# Sheet1.net
KiCad netlist of a schematic drawn in Altium Designer
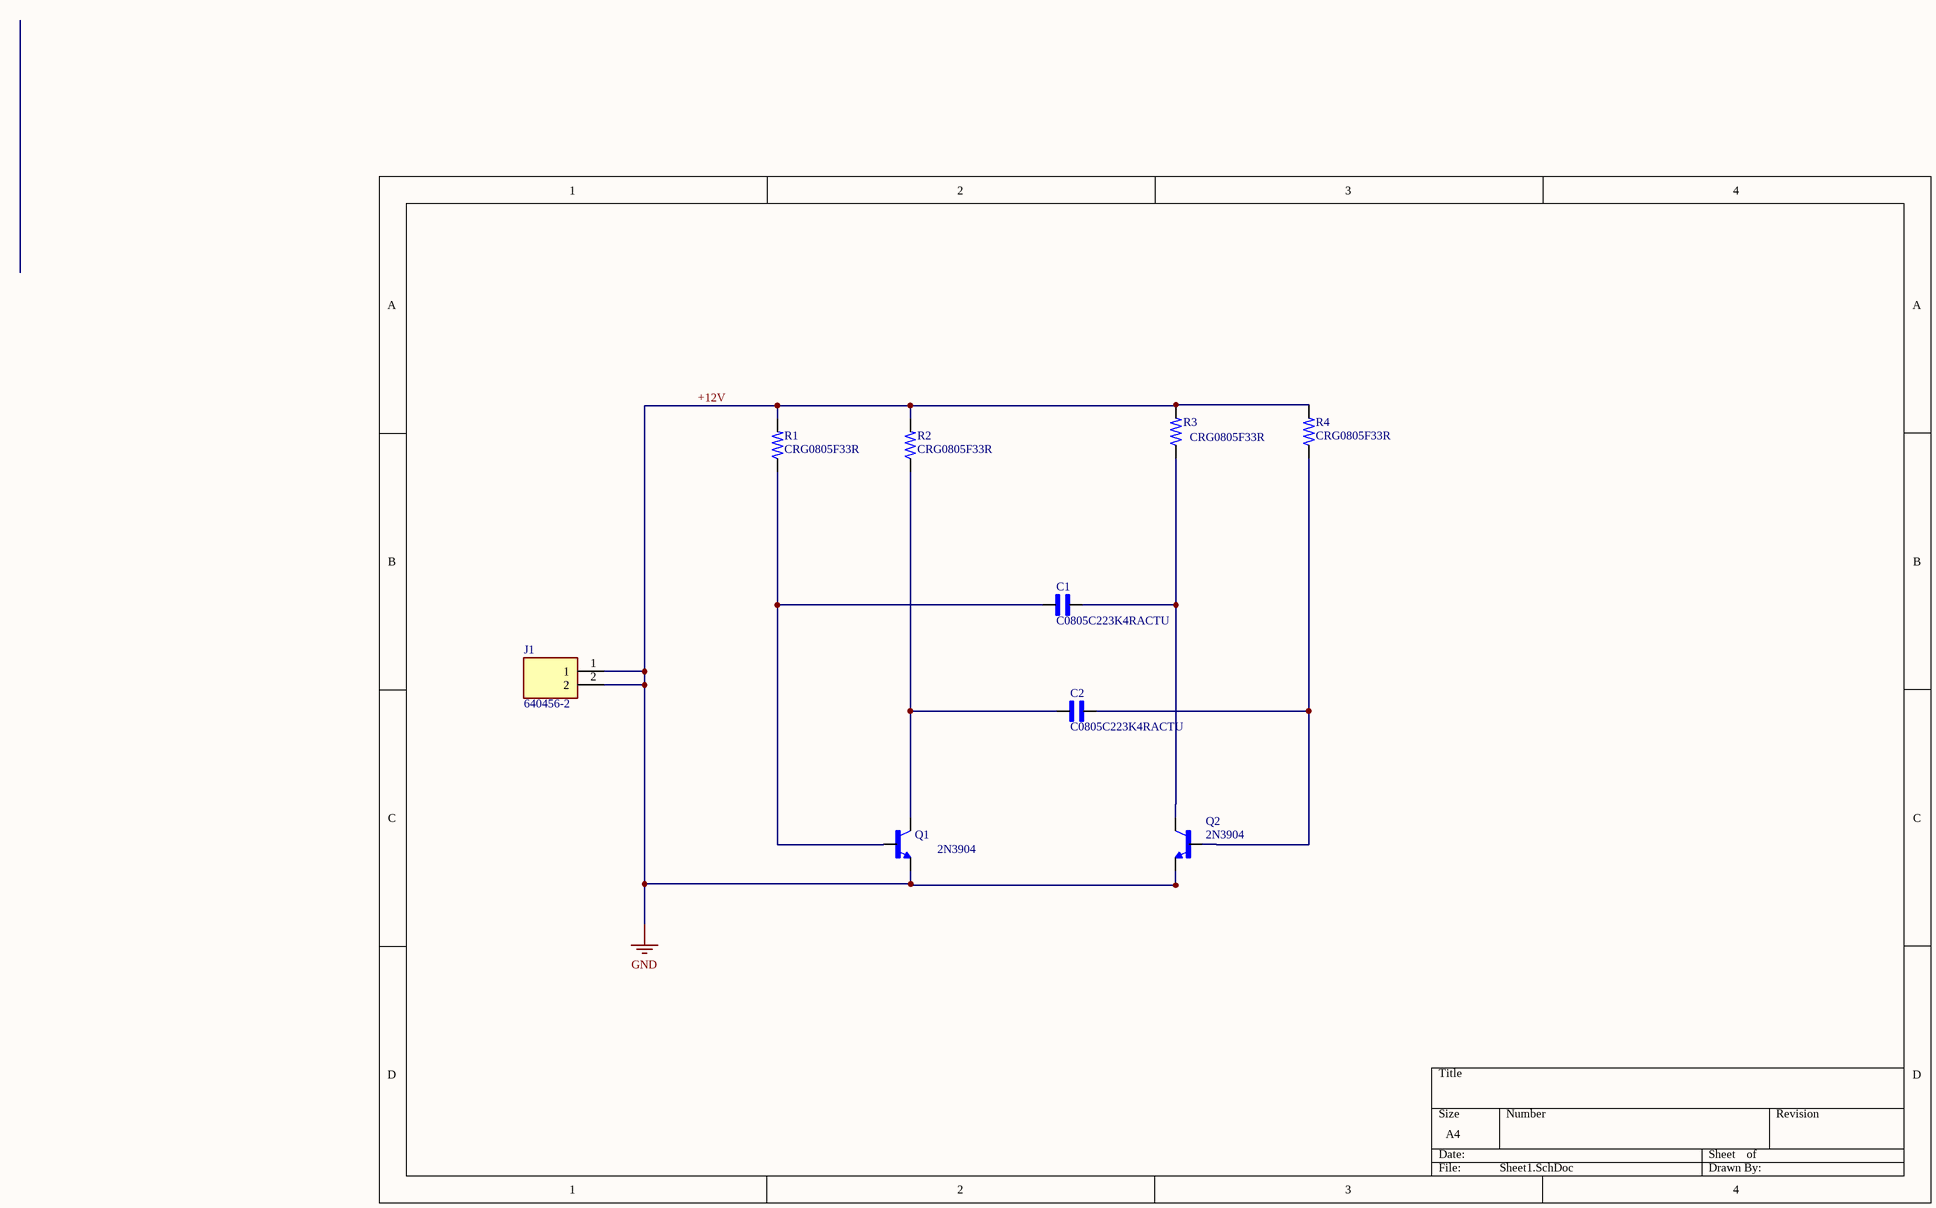
[diagram p0: Sheet1.SchDoc]

(export (version "E")
  (design (tool "Eeschema 10.0.6"))
  (components
    (comp (ref "C1")
      (value "C0805C223K4RACTU")
      (footprint "CAPC2012X88N")
      (description "Capacitor, Ceramic, 22nF, 16VDC, 10-% Tol, 10+% Tol, X7R-TC Code, -15, 15%-TC")
      (fields (field (name "MF") "KEMET"))
      (libsource (lib "C0805C223K4RACTU") (part "C0805C223K4RACTU"))
    )
    (comp (ref "C2")
      (value "C0805C223K4RACTU")
      (footprint "CAPC2012X88N")
      (description "Capacitor, Ceramic, 22nF, 16VDC, 10-% Tol, 10+% Tol, X7R-TC Code, -15, 15%-TC")
      (fields (field (name "MF") "KEMET"))
      (libsource (lib "C0805C223K4RACTU") (part "C0805C223K4RACTU"))
    )
    (comp (ref "J1")
      (value "640456-2")
      (footprint "TE_640456-2")
      (description "Header Friction Lock MTA-100 2 250 VAC Polyester Tin Copper Alloy Tin ¦ TE Connectivity 640456-2")
      (fields (field (name "MF") "TE Connectivity"))
      (libsource (lib "header") (part "640456-2"))
    )
    (comp (ref "Q1")
      (value "2N3904")
      (footprint "TO92254P460H750-3")
      (description "BJT, TO-92, 40V, 200mA, NPN, 0.625W, 150Â°C")
      (fields (field (name "MF") "Diotec Semiconductor"))
      (libsource (lib "2N3904") (part "2N3904"))
    )
    (comp (ref "Q2")
      (value "2N3904")
      (footprint "TO92254P460H750-3")
      (description "BJT, TO-92, 40V, 200mA, NPN, 0.625W, 150Â°C")
      (fields (field (name "MF") "Diotec Semiconductor"))
      (libsource (lib "") (part "2N3904_1"))
    )
    (comp (ref "R1")
      (value "CRG0805F33R")
      (footprint "RESC2012X65N")
      (description "Fixed Resistors")
      (fields (field (name "MF") "TE Connectivity"))
      (libsource (lib "CRG0805F33R") (part "CRG0805F33R"))
    )
    (comp (ref "R2")
      (value "CRG0805F33R")
      (footprint "RESC2012X65N")
      (description "Fixed Resistors")
      (fields (field (name "MF") "TE Connectivity"))
      (libsource (lib "CRG0805F33R") (part "CRG0805F33R"))
    )
    (comp (ref "R3")
      (value "CRG0805F33R")
      (footprint "RESC2012X65N")
      (description "Fixed Resistors")
      (fields (field (name "MF") "TE Connectivity"))
      (libsource (lib "CRG0805F33R") (part "CRG0805F33R"))
    )
    (comp (ref "R4")
      (value "CRG0805F33R")
      (footprint "RESC2012X65N")
      (description "Fixed Resistors")
      (fields (field (name "MF") "TE Connectivity"))
      (libsource (lib "CRG0805F33R") (part "CRG0805F33R"))
    )
  )
  (nets
    (net (code "1") (name "GND") (class "Default")
      (node (ref "J1") (pin "1") (pinfunction "1_1") (pintype "passive"))
      (node (ref "J1") (pin "2") (pinfunction "2_2") (pintype "passive"))
      (node (ref "Q1") (pin "1") (pinfunction "E_1") (pintype "passive"))
      (node (ref "Q2") (pin "1") (pinfunction "E_1") (pintype "passive"))
      (node (ref "R1") (pin "2") (pinfunction "2_2") (pintype "passive"))
      (node (ref "R2") (pin "2") (pinfunction "2_2") (pintype "passive"))
      (node (ref "R3") (pin "2") (pinfunction "2_2") (pintype "passive"))
      (node (ref "R4") (pin "2") (pinfunction "2_2") (pintype "passive"))
    )
    (net (code "2") (name "Net-(Q1-B)") (class "Default")
      (node (ref "C1") (pin "2") (pinfunction "2_2") (pintype "passive"))
      (node (ref "Q1") (pin "2") (pinfunction "B_2") (pintype "passive"))
      (node (ref "R1") (pin "1") (pinfunction "1_1") (pintype "passive"))
    )
    (net (code "3") (name "Net-(Q1-C)") (class "Default")
      (node (ref "C2") (pin "2") (pinfunction "2_2") (pintype "passive"))
      (node (ref "Q1") (pin "3") (pinfunction "C_3") (pintype "passive"))
      (node (ref "R2") (pin "1") (pinfunction "1_1") (pintype "passive"))
    )
    (net (code "4") (name "Net-(Q2-B)") (class "Default")
      (node (ref "C2") (pin "1") (pinfunction "1_1") (pintype "passive"))
      (node (ref "Q2") (pin "2") (pinfunction "B_2") (pintype "passive"))
      (node (ref "R4") (pin "1") (pinfunction "1_1") (pintype "passive"))
    )
    (net (code "5") (name "Net-(Q2-C)") (class "Default")
      (node (ref "C1") (pin "1") (pinfunction "1_1") (pintype "passive"))
      (node (ref "Q2") (pin "3") (pinfunction "C_3") (pintype "passive"))
      (node (ref "R3") (pin "1") (pinfunction "1_1") (pintype "passive"))
    )
  )
)
